# ab_sch.net
KiCad netlist of a schematic drawn in EAGLE
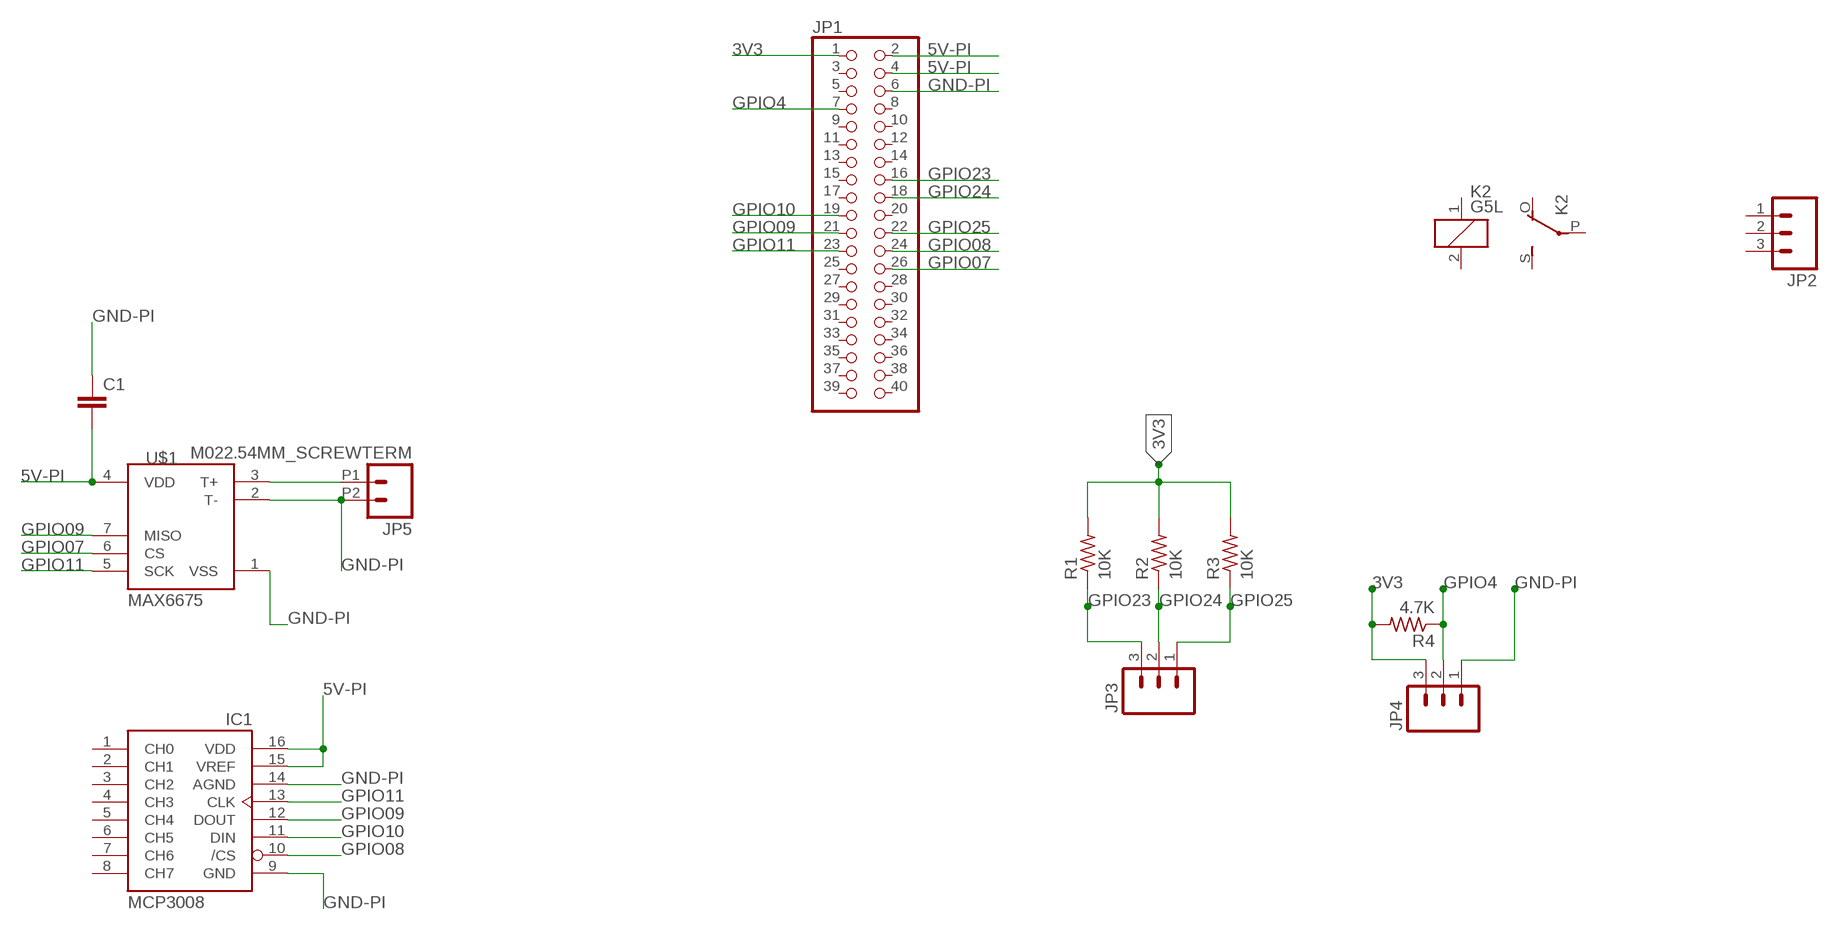
[diagram p0: schematic, sheet 1]

(export (version "E")
  (design (tool "Eeschema 10.0.6"))
  (components
    (comp (ref "C1")
      (value "CAPKIT")
      (footprint "eagle-import:CAP-PTH-SMALL-KIT")
      (libsource (lib "eagle-import") (part "CAPKIT"))
    )
    (comp (ref "IC1")
      (value "MCP3008")
      (footprint "eagle-import:DIL16")
      (libsource (lib "eagle-import") (part "MCP3008"))
    )
    (comp (ref "JP1")
      (value "PINHD-2X20")
      (footprint "eagle-import:2X20")
      (libsource (lib "eagle-import") (part "PINHD-2X20"))
    )
    (comp (ref "JP2")
      (value "M03SCREW")
      (footprint "eagle-import:SCREWTERMINAL-3.5MM-3")
      (libsource (lib "eagle-import") (part "M03SCREW"))
    )
    (comp (ref "JP3")
      (value "M03SCREW")
      (footprint "eagle-import:SCREWTERMINAL-3.5MM-3")
      (libsource (lib "eagle-import") (part "M03SCREW"))
    )
    (comp (ref "JP4")
      (value "M03SCREW")
      (footprint "eagle-import:SCREWTERMINAL-3.5MM-3")
      (libsource (lib "eagle-import") (part "M03SCREW"))
    )
    (comp (ref "JP5")
      (value "M022.54MM_SCREWTERM")
      (footprint "eagle-import:1X02_2.54_SCREWTERM")
      (libsource (lib "eagle-import") (part "M022.54MM_SCREWTERM"))
    )
    (comp (ref "K2")
      (value "G5L")
      (footprint "eagle-import:G5LE")
      (libsource (lib "eagle-import") (part "G5L"))
    )
    (comp (ref "R1")
      (value "10K")
      (footprint "eagle-import:0207_10")
      (libsource (lib "eagle-import") (part "R-US_0207/10"))
    )
    (comp (ref "R2")
      (value "10K")
      (footprint "eagle-import:0207_10")
      (libsource (lib "eagle-import") (part "R-US_0207/10"))
    )
    (comp (ref "R3")
      (value "10K")
      (footprint "eagle-import:0207_10")
      (libsource (lib "eagle-import") (part "R-US_0207/10"))
    )
    (comp (ref "R4")
      (value "4.7K")
      (footprint "eagle-import:0207_10")
      (libsource (lib "eagle-import") (part "R-US_0207/10"))
    )
    (comp (ref "U$1")
      (value "MAX6675")
      (footprint "eagle-import:SO08-MAX6675")
      (libsource (lib "eagle-import") (part "MAX6675"))
    )
  )
  (nets
    (net (code "1") (name "/5V-PI") (class "Default")
      (node (ref "C1") (pin "2") (pinfunction "2_2") (pintype "passive"))
      (node (ref "IC1") (pin "15") (pinfunction "VREF_15") (pintype "input"))
      (node (ref "IC1") (pin "16") (pinfunction "VDD_16") (pintype "power_in"))
      (node (ref "JP1") (pin "2") (pinfunction "2_2") (pintype "passive"))
      (node (ref "JP1") (pin "4") (pinfunction "4_4") (pintype "passive"))
      (node (ref "U$1") (pin "4") (pinfunction "VDD_4") (pintype "bidirectional"))
    )
    (net (code "2") (name "/GND-PI") (class "Default")
      (node (ref "C1") (pin "1") (pinfunction "1_1") (pintype "passive"))
      (node (ref "IC1") (pin "14") (pinfunction "AGND_14") (pintype "power_in"))
      (node (ref "IC1") (pin "9") (pinfunction "GND_9") (pintype "power_in"))
      (node (ref "JP1") (pin "6") (pinfunction "6_6") (pintype "passive"))
      (node (ref "JP4") (pin "1") (pinfunction "1_1") (pintype "passive"))
      (node (ref "JP5") (pin "P2") (pinfunction "2_P2") (pintype "passive"))
      (node (ref "U$1") (pin "1") (pinfunction "VSS_1") (pintype "bidirectional"))
      (node (ref "U$1") (pin "2") (pinfunction "T-_2") (pintype "bidirectional"))
    )
    (net (code "3") (name "/GPIO4") (class "Default")
      (node (ref "JP1") (pin "7") (pinfunction "7_7") (pintype "passive"))
      (node (ref "JP4") (pin "2") (pinfunction "2_2") (pintype "passive"))
      (node (ref "R4") (pin "1") (pinfunction "1_1") (pintype "passive"))
    )
    (net (code "4") (name "/GPIO07") (class "Default")
      (node (ref "JP1") (pin "26") (pinfunction "26_26") (pintype "passive"))
      (node (ref "U$1") (pin "6") (pinfunction "CS_6") (pintype "bidirectional"))
    )
    (net (code "5") (name "/GPIO08") (class "Default")
      (node (ref "IC1") (pin "10") (pinfunction "/CS_10") (pintype "input"))
      (node (ref "JP1") (pin "24") (pinfunction "24_24") (pintype "passive"))
    )
    (net (code "6") (name "/GPIO09") (class "Default")
      (node (ref "IC1") (pin "12") (pinfunction "DOUT_12") (pintype "output"))
      (node (ref "JP1") (pin "21") (pinfunction "21_21") (pintype "passive"))
      (node (ref "U$1") (pin "7") (pinfunction "MISO_7") (pintype "bidirectional"))
    )
    (net (code "7") (name "/GPIO10") (class "Default")
      (node (ref "IC1") (pin "11") (pinfunction "DIN_11") (pintype "input"))
      (node (ref "JP1") (pin "19") (pinfunction "19_19") (pintype "passive"))
    )
    (net (code "8") (name "/GPIO11") (class "Default")
      (node (ref "IC1") (pin "13") (pinfunction "CLK_13") (pintype "input"))
      (node (ref "JP1") (pin "23") (pinfunction "23_23") (pintype "passive"))
      (node (ref "U$1") (pin "5") (pinfunction "SCK_5") (pintype "bidirectional"))
    )
    (net (code "9") (name "/GPIO23") (class "Default")
      (node (ref "JP1") (pin "16") (pinfunction "16_16") (pintype "passive"))
      (node (ref "JP3") (pin "3") (pinfunction "3_3") (pintype "passive"))
      (node (ref "R1") (pin "1") (pinfunction "1_1") (pintype "passive"))
    )
    (net (code "10") (name "/GPIO24") (class "Default")
      (node (ref "JP1") (pin "18") (pinfunction "18_18") (pintype "passive"))
      (node (ref "JP3") (pin "2") (pinfunction "2_2") (pintype "passive"))
      (node (ref "R2") (pin "1") (pinfunction "1_1") (pintype "passive"))
    )
    (net (code "11") (name "/GPIO25") (class "Default")
      (node (ref "JP1") (pin "22") (pinfunction "22_22") (pintype "passive"))
      (node (ref "JP3") (pin "1") (pinfunction "1_1") (pintype "passive"))
      (node (ref "R3") (pin "1") (pinfunction "1_1") (pintype "passive"))
    )
    (net (code "12") (name "3V3") (class "Default")
      (node (ref "JP1") (pin "1") (pinfunction "3V3_1") (pintype "passive"))
      (node (ref "JP4") (pin "3") (pinfunction "3_3") (pintype "passive"))
      (node (ref "R1") (pin "2") (pinfunction "2_2") (pintype "passive"))
      (node (ref "R2") (pin "2") (pinfunction "2_2") (pintype "passive"))
      (node (ref "R3") (pin "2") (pinfunction "2_2") (pintype "passive"))
      (node (ref "R4") (pin "2") (pinfunction "2_2") (pintype "passive"))
    )
    (net (code "13") (name "Net-(JP5-1)") (class "Default")
      (node (ref "JP5") (pin "P1") (pinfunction "1_P1") (pintype "passive"))
      (node (ref "U$1") (pin "3") (pinfunction "T+_3") (pintype "bidirectional"))
    )
    (net (code "14") (name "unconnected-(IC1-CH0-Pad1)") (class "Default")
      (node (ref "IC1") (pin "1") (pinfunction "CH0_1") (pintype "input"))
    )
    (net (code "15") (name "unconnected-(IC1-CH1-Pad2)") (class "Default")
      (node (ref "IC1") (pin "2") (pinfunction "CH1_2") (pintype "input"))
    )
    (net (code "16") (name "unconnected-(IC1-CH2-Pad3)") (class "Default")
      (node (ref "IC1") (pin "3") (pinfunction "CH2_3") (pintype "input"))
    )
    (net (code "17") (name "unconnected-(IC1-CH3-Pad4)") (class "Default")
      (node (ref "IC1") (pin "4") (pinfunction "CH3_4") (pintype "input"))
    )
    (net (code "18") (name "unconnected-(IC1-CH4-Pad5)") (class "Default")
      (node (ref "IC1") (pin "5") (pinfunction "CH4_5") (pintype "input"))
    )
    (net (code "19") (name "unconnected-(IC1-CH5-Pad6)") (class "Default")
      (node (ref "IC1") (pin "6") (pinfunction "CH5_6") (pintype "input"))
    )
    (net (code "20") (name "unconnected-(IC1-CH6-Pad7)") (class "Default")
      (node (ref "IC1") (pin "7") (pinfunction "CH6_7") (pintype "input"))
    )
    (net (code "21") (name "unconnected-(IC1-CH7-Pad8)") (class "Default")
      (node (ref "IC1") (pin "8") (pinfunction "CH7_8") (pintype "input"))
    )
    (net (code "22") (name "unconnected-(JP1-Pad3)") (class "Default")
      (node (ref "JP1") (pin "3") (pinfunction "3_3") (pintype "passive"))
    )
    (net (code "23") (name "unconnected-(JP1-Pad5)") (class "Default")
      (node (ref "JP1") (pin "5") (pinfunction "5_5") (pintype "passive"))
    )
    (net (code "24") (name "unconnected-(JP1-Pad8)") (class "Default")
      (node (ref "JP1") (pin "8") (pinfunction "8_8") (pintype "passive"))
    )
    (net (code "25") (name "unconnected-(JP1-Pad9)") (class "Default")
      (node (ref "JP1") (pin "9") (pinfunction "9_9") (pintype "passive"))
    )
    (net (code "26") (name "unconnected-(JP1-Pad10)") (class "Default")
      (node (ref "JP1") (pin "10") (pinfunction "10_10") (pintype "passive"))
    )
    (net (code "27") (name "unconnected-(JP1-Pad11)") (class "Default")
      (node (ref "JP1") (pin "11") (pinfunction "11_11") (pintype "passive"))
    )
    (net (code "28") (name "unconnected-(JP1-Pad12)") (class "Default")
      (node (ref "JP1") (pin "12") (pinfunction "12_12") (pintype "passive"))
    )
    (net (code "29") (name "unconnected-(JP1-Pad13)") (class "Default")
      (node (ref "JP1") (pin "13") (pinfunction "13_13") (pintype "passive"))
    )
    (net (code "30") (name "unconnected-(JP1-Pad14)") (class "Default")
      (node (ref "JP1") (pin "14") (pinfunction "14_14") (pintype "passive"))
    )
    (net (code "31") (name "unconnected-(JP1-Pad15)") (class "Default")
      (node (ref "JP1") (pin "15") (pinfunction "15_15") (pintype "passive"))
    )
    (net (code "32") (name "unconnected-(JP1-Pad17)") (class "Default")
      (node (ref "JP1") (pin "17") (pinfunction "17_17") (pintype "passive"))
    )
    (net (code "33") (name "unconnected-(JP1-Pad20)") (class "Default")
      (node (ref "JP1") (pin "20") (pinfunction "20_20") (pintype "passive"))
    )
    (net (code "34") (name "unconnected-(JP1-Pad25)") (class "Default")
      (node (ref "JP1") (pin "25") (pinfunction "25_25") (pintype "passive"))
    )
    (net (code "35") (name "unconnected-(JP1-Pad27)") (class "Default")
      (node (ref "JP1") (pin "27") (pinfunction "27_27") (pintype "passive"))
    )
    (net (code "36") (name "unconnected-(JP1-Pad28)") (class "Default")
      (node (ref "JP1") (pin "28") (pinfunction "28_28") (pintype "passive"))
    )
    (net (code "37") (name "unconnected-(JP1-Pad29)") (class "Default")
      (node (ref "JP1") (pin "29") (pinfunction "29_29") (pintype "passive"))
    )
    (net (code "38") (name "unconnected-(JP1-Pad30)") (class "Default")
      (node (ref "JP1") (pin "30") (pinfunction "30_30") (pintype "passive"))
    )
    (net (code "39") (name "unconnected-(JP1-Pad31)") (class "Default")
      (node (ref "JP1") (pin "31") (pinfunction "31_31") (pintype "passive"))
    )
    (net (code "40") (name "unconnected-(JP1-Pad32)") (class "Default")
      (node (ref "JP1") (pin "32") (pinfunction "32_32") (pintype "passive"))
    )
    (net (code "41") (name "unconnected-(JP1-Pad33)") (class "Default")
      (node (ref "JP1") (pin "33") (pinfunction "33_33") (pintype "passive"))
    )
    (net (code "42") (name "unconnected-(JP1-Pad34)") (class "Default")
      (node (ref "JP1") (pin "34") (pinfunction "34_34") (pintype "passive"))
    )
    (net (code "43") (name "unconnected-(JP1-Pad35)") (class "Default")
      (node (ref "JP1") (pin "35") (pinfunction "35_35") (pintype "passive"))
    )
    (net (code "44") (name "unconnected-(JP1-Pad36)") (class "Default")
      (node (ref "JP1") (pin "36") (pinfunction "36_36") (pintype "passive"))
    )
    (net (code "45") (name "unconnected-(JP1-Pad37)") (class "Default")
      (node (ref "JP1") (pin "37") (pinfunction "37_37") (pintype "passive"))
    )
    (net (code "46") (name "unconnected-(JP1-Pad38)") (class "Default")
      (node (ref "JP1") (pin "38") (pinfunction "38_38") (pintype "passive"))
    )
    (net (code "47") (name "unconnected-(JP1-Pad39)") (class "Default")
      (node (ref "JP1") (pin "39") (pinfunction "39_39") (pintype "passive"))
    )
    (net (code "48") (name "unconnected-(JP1-Pad40)") (class "Default")
      (node (ref "JP1") (pin "40") (pinfunction "40_40") (pintype "passive"))
    )
    (net (code "49") (name "unconnected-(JP2-Pad1)") (class "Default")
      (node (ref "JP2") (pin "1") (pinfunction "1_1") (pintype "passive"))
    )
    (net (code "50") (name "unconnected-(JP2-Pad2)") (class "Default")
      (node (ref "JP2") (pin "2") (pinfunction "2_2") (pintype "passive"))
    )
    (net (code "51") (name "unconnected-(JP2-Pad3)") (class "Default")
      (node (ref "JP2") (pin "3") (pinfunction "3_3") (pintype "passive"))
    )
    (net (code "52") (name "unconnected-(K2-Pad1)") (class "Default")
      (node (ref "K2") (pin "1") (pinfunction "1_1") (pintype "passive"))
    )
    (net (code "53") (name "unconnected-(K2-Pad2)") (class "Default")
      (node (ref "K2") (pin "2") (pinfunction "2_2") (pintype "passive"))
    )
    (net (code "54") (name "unconnected-(K2-PadO)") (class "Default")
      (node (ref "K2") (pin "O") (pinfunction "O_O") (pintype "passive"))
    )
    (net (code "55") (name "unconnected-(K2-PadP)") (class "Default")
      (node (ref "K2") (pin "P") (pinfunction "P_P") (pintype "passive"))
    )
    (net (code "56") (name "unconnected-(K2-PadS)") (class "Default")
      (node (ref "K2") (pin "S") (pinfunction "S_S") (pintype "passive"))
    )
  )
)
